# MotorController_ToniDove_Full05.net
KiCad netlist of a schematic drawn in EAGLE
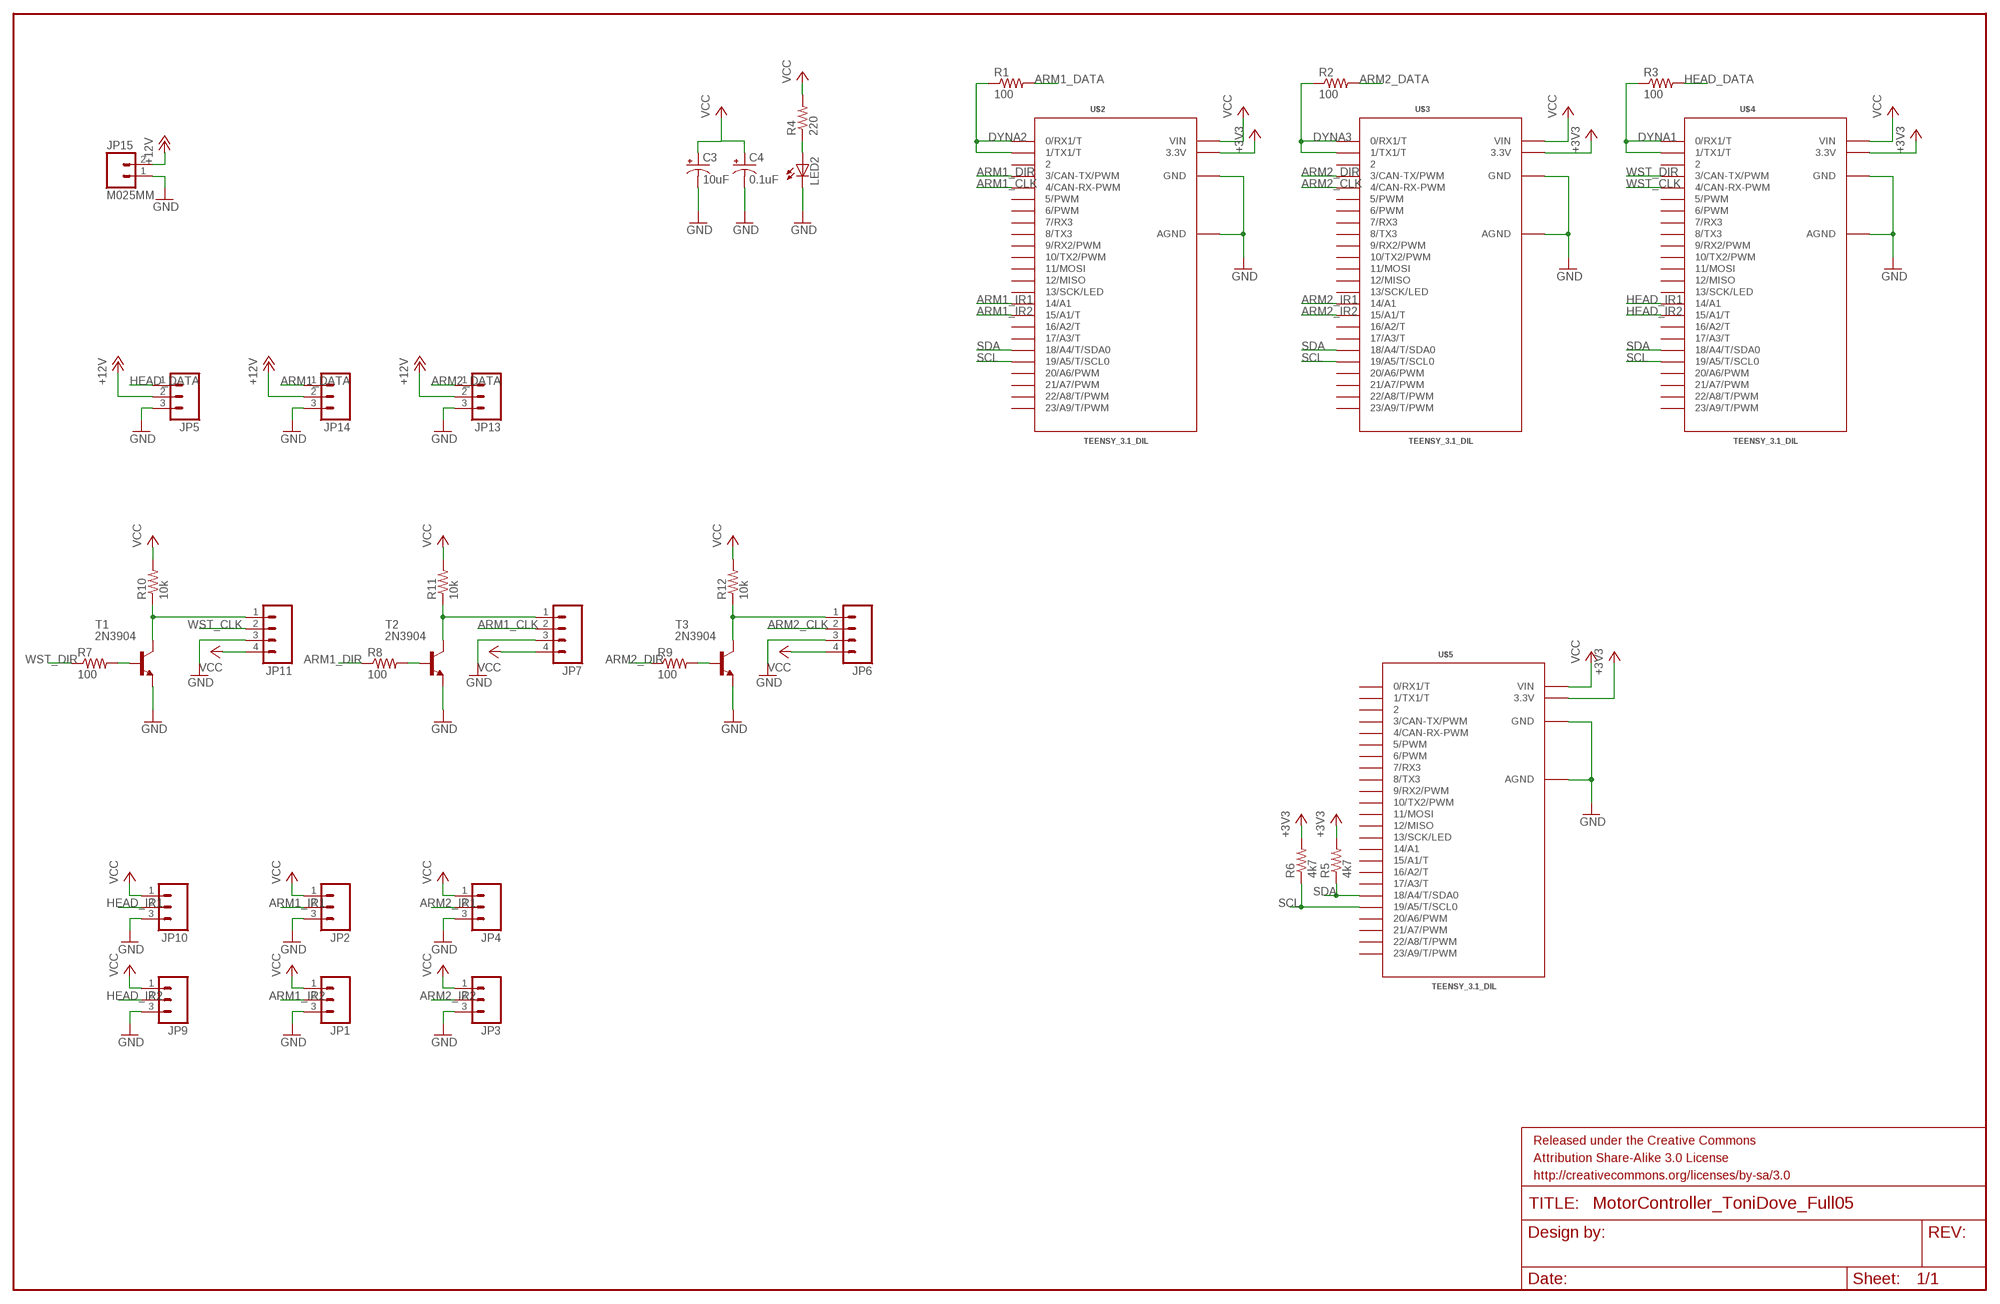
[diagram p0: schematic, sheet 1]

(export (version "E")
  (design (tool "Eeschema 10.0.6"))
  (components
    (comp (ref "C3")
      (value "10uF")
      (footprint "eagle-import:E2,5-6E")
      (libsource (lib "eagle-import") (part "CPOL-USE2,5-6E"))
    )
    (comp (ref "C4")
      (value "0.1uF")
      (footprint "eagle-import:E2,5-6E")
      (libsource (lib "eagle-import") (part "CPOL-USE2,5-6E"))
    )
    (comp (ref "FRAME1")
      (value "FRAME-LEDGER")
      (footprint "eagle-import:CREATIVE_COMMONS")
      (libsource (lib "eagle-import") (part "FRAME-LEDGER"))
    )
    (comp (ref "JP1")
      (value "M03PTH")
      (footprint "eagle-import:1X03")
      (libsource (lib "eagle-import") (part "M03PTH"))
    )
    (comp (ref "JP2")
      (value "M03PTH")
      (footprint "eagle-import:1X03")
      (libsource (lib "eagle-import") (part "M03PTH"))
    )
    (comp (ref "JP3")
      (value "M03PTH")
      (footprint "eagle-import:1X03")
      (libsource (lib "eagle-import") (part "M03PTH"))
    )
    (comp (ref "JP4")
      (value "M03PTH")
      (footprint "eagle-import:1X03")
      (libsource (lib "eagle-import") (part "M03PTH"))
    )
    (comp (ref "JP5")
      (value "M03PTH")
      (footprint "eagle-import:1X03")
      (libsource (lib "eagle-import") (part "M03PTH"))
    )
    (comp (ref "JP6")
      (value "M04SCREW")
      (footprint "eagle-import:SCREWTERMINAL-3.5MM-4")
      (libsource (lib "eagle-import") (part "M04SCREW"))
    )
    (comp (ref "JP7")
      (value "M04SCREW")
      (footprint "eagle-import:SCREWTERMINAL-3.5MM-4")
      (libsource (lib "eagle-import") (part "M04SCREW"))
    )
    (comp (ref "JP9")
      (value "M03PTH")
      (footprint "eagle-import:1X03")
      (libsource (lib "eagle-import") (part "M03PTH"))
    )
    (comp (ref "JP10")
      (value "M03PTH")
      (footprint "eagle-import:1X03")
      (libsource (lib "eagle-import") (part "M03PTH"))
    )
    (comp (ref "JP11")
      (value "M04SCREW")
      (footprint "eagle-import:SCREWTERMINAL-3.5MM-4")
      (libsource (lib "eagle-import") (part "M04SCREW"))
    )
    (comp (ref "JP13")
      (value "M03PTH")
      (footprint "eagle-import:1X03")
      (libsource (lib "eagle-import") (part "M03PTH"))
    )
    (comp (ref "JP14")
      (value "M03PTH")
      (footprint "eagle-import:1X03")
      (libsource (lib "eagle-import") (part "M03PTH"))
    )
    (comp (ref "JP15")
      (value "M025MM")
      (footprint "eagle-import:SCREWTERMINAL-5MM-2")
      (libsource (lib "eagle-import") (part "M025MM"))
    )
    (comp (ref "LED2")
      (value "LED5MM")
      (footprint "eagle-import:LED5MM")
      (libsource (lib "eagle-import") (part "LED5MM"))
    )
    (comp (ref "R1")
      (value "100")
      (footprint "eagle-import:0204_7")
      (libsource (lib "eagle-import") (part "R-US_0204/7"))
    )
    (comp (ref "R2")
      (value "100")
      (footprint "eagle-import:0204_7")
      (libsource (lib "eagle-import") (part "R-US_0204/7"))
    )
    (comp (ref "R3")
      (value "100")
      (footprint "eagle-import:0204_7")
      (libsource (lib "eagle-import") (part "R-US_0204/7"))
    )
    (comp (ref "R4")
      (value "220")
      (footprint "eagle-import:0204_7")
      (libsource (lib "eagle-import") (part "R-US_0204/7"))
    )
    (comp (ref "R5")
      (value "4k7")
      (footprint "eagle-import:0204_7")
      (libsource (lib "eagle-import") (part "R-US_0204/7"))
    )
    (comp (ref "R6")
      (value "4k7")
      (footprint "eagle-import:0204_7")
      (libsource (lib "eagle-import") (part "R-US_0204/7"))
    )
    (comp (ref "R7")
      (value "100")
      (footprint "eagle-import:0204_7")
      (libsource (lib "eagle-import") (part "R-US_0204/7"))
    )
    (comp (ref "R8")
      (value "100")
      (footprint "eagle-import:0204_7")
      (libsource (lib "eagle-import") (part "R-US_0204/7"))
    )
    (comp (ref "R9")
      (value "100")
      (footprint "eagle-import:0204_7")
      (libsource (lib "eagle-import") (part "R-US_0204/7"))
    )
    (comp (ref "R10")
      (value "10k")
      (footprint "eagle-import:0204_7")
      (libsource (lib "eagle-import") (part "R-US_0204/7"))
    )
    (comp (ref "R11")
      (value "10k")
      (footprint "eagle-import:0204_7")
      (libsource (lib "eagle-import") (part "R-US_0204/7"))
    )
    (comp (ref "R12")
      (value "10k")
      (footprint "eagle-import:0204_7")
      (libsource (lib "eagle-import") (part "R-US_0204/7"))
    )
    (comp (ref "T1")
      (value "2N3904")
      (footprint "eagle-import:TO92")
      (libsource (lib "eagle-import") (part "2N3904"))
    )
    (comp (ref "T2")
      (value "2N3904")
      (footprint "eagle-import:TO92")
      (libsource (lib "eagle-import") (part "2N3904"))
    )
    (comp (ref "T3")
      (value "2N3904")
      (footprint "eagle-import:TO92")
      (libsource (lib "eagle-import") (part "2N3904"))
    )
    (comp (ref "U$2")
      (value "TEENSY_3.1_DIL")
      (footprint "eagle-import:TEENSY3-DIL")
      (libsource (lib "eagle-import") (part "TEENSY_3.1_DIL"))
    )
    (comp (ref "U$3")
      (value "TEENSY_3.1_DIL")
      (footprint "eagle-import:TEENSY3-DIL")
      (libsource (lib "eagle-import") (part "TEENSY_3.1_DIL"))
    )
    (comp (ref "U$4")
      (value "TEENSY_3.1_DIL")
      (footprint "eagle-import:TEENSY3-DIL")
      (libsource (lib "eagle-import") (part "TEENSY_3.1_DIL"))
    )
    (comp (ref "U$5")
      (value "TEENSY_3.1_DIL")
      (footprint "eagle-import:TEENSY3-DIL")
      (libsource (lib "eagle-import") (part "TEENSY_3.1_DIL"))
    )
  )
  (nets
    (net (code "1") (name "+3V3") (class "Default")
      (node (ref "R5") (pin "2") (pinfunction "2_2") (pintype "passive"))
      (node (ref "R6") (pin "2") (pinfunction "2_2") (pintype "passive"))
      (node (ref "U$2") (pin "3.3V") (pinfunction "3.3V_3.3V") (pintype "power_in"))
      (node (ref "U$3") (pin "3.3V") (pinfunction "3.3V_3.3V") (pintype "power_in"))
      (node (ref "U$4") (pin "3.3V") (pinfunction "3.3V_3.3V") (pintype "power_in"))
      (node (ref "U$5") (pin "3.3V") (pinfunction "3.3V_3.3V") (pintype "power_in"))
    )
    (net (code "2") (name "+12V") (class "Default")
      (node (ref "JP13") (pin "2") (pinfunction "2_2") (pintype "passive"))
      (node (ref "JP14") (pin "2") (pinfunction "2_2") (pintype "passive"))
      (node (ref "JP15") (pin "2") (pinfunction "2_2") (pintype "passive"))
      (node (ref "JP5") (pin "2") (pinfunction "2_2") (pintype "passive"))
    )
    (net (code "3") (name "/ARM1_CLK") (class "Default")
      (node (ref "JP7") (pin "2") (pinfunction "2_2") (pintype "passive"))
      (node (ref "U$2") (pin "4") (pinfunction "4/CAN-RX-PWM_4") (pintype "bidirectional"))
    )
    (net (code "4") (name "/ARM1_DATA") (class "Default")
      (node (ref "JP14") (pin "1") (pinfunction "1_1") (pintype "passive"))
      (node (ref "R1") (pin "2") (pinfunction "2_2") (pintype "passive"))
    )
    (net (code "5") (name "/ARM1_DIR") (class "Default")
      (node (ref "R8") (pin "1") (pinfunction "1_1") (pintype "passive"))
      (node (ref "U$2") (pin "3") (pinfunction "3/CAN-TX/PWM_3") (pintype "bidirectional"))
    )
    (net (code "6") (name "/ARM1_IR1") (class "Default")
      (node (ref "JP2") (pin "2") (pinfunction "2_2") (pintype "passive"))
      (node (ref "U$2") (pin "14/A0") (pinfunction "14/A1_14/A0") (pintype "bidirectional"))
    )
    (net (code "7") (name "/ARM1_IR2") (class "Default")
      (node (ref "JP1") (pin "2") (pinfunction "2_2") (pintype "passive"))
      (node (ref "U$2") (pin "15/A1") (pinfunction "15/A1/T_15/A1") (pintype "bidirectional"))
    )
    (net (code "8") (name "/ARM2_CLK") (class "Default")
      (node (ref "JP6") (pin "2") (pinfunction "2_2") (pintype "passive"))
      (node (ref "U$3") (pin "4") (pinfunction "4/CAN-RX-PWM_4") (pintype "bidirectional"))
    )
    (net (code "9") (name "/ARM2_DATA") (class "Default")
      (node (ref "JP13") (pin "1") (pinfunction "1_1") (pintype "passive"))
      (node (ref "R2") (pin "2") (pinfunction "2_2") (pintype "passive"))
    )
    (net (code "10") (name "/ARM2_DIR") (class "Default")
      (node (ref "R9") (pin "1") (pinfunction "1_1") (pintype "passive"))
      (node (ref "U$3") (pin "3") (pinfunction "3/CAN-TX/PWM_3") (pintype "bidirectional"))
    )
    (net (code "11") (name "/ARM2_IR1") (class "Default")
      (node (ref "JP4") (pin "2") (pinfunction "2_2") (pintype "passive"))
      (node (ref "U$3") (pin "14/A0") (pinfunction "14/A1_14/A0") (pintype "bidirectional"))
    )
    (net (code "12") (name "/ARM2_IR2") (class "Default")
      (node (ref "JP3") (pin "2") (pinfunction "2_2") (pintype "passive"))
      (node (ref "U$3") (pin "15/A1") (pinfunction "15/A1/T_15/A1") (pintype "bidirectional"))
    )
    (net (code "13") (name "/DYNA1") (class "Default")
      (node (ref "R3") (pin "1") (pinfunction "1_1") (pintype "passive"))
      (node (ref "U$4") (pin "0") (pinfunction "0/RX1/T_0") (pintype "bidirectional"))
      (node (ref "U$4") (pin "1") (pinfunction "1/TX1/T_1") (pintype "bidirectional"))
    )
    (net (code "14") (name "/DYNA2") (class "Default")
      (node (ref "R1") (pin "1") (pinfunction "1_1") (pintype "passive"))
      (node (ref "U$2") (pin "0") (pinfunction "0/RX1/T_0") (pintype "bidirectional"))
      (node (ref "U$2") (pin "1") (pinfunction "1/TX1/T_1") (pintype "bidirectional"))
    )
    (net (code "15") (name "/DYNA3") (class "Default")
      (node (ref "R2") (pin "1") (pinfunction "1_1") (pintype "passive"))
      (node (ref "U$3") (pin "0") (pinfunction "0/RX1/T_0") (pintype "bidirectional"))
      (node (ref "U$3") (pin "1") (pinfunction "1/TX1/T_1") (pintype "bidirectional"))
    )
    (net (code "16") (name "/HEAD_DATA") (class "Default")
      (node (ref "JP5") (pin "1") (pinfunction "1_1") (pintype "passive"))
      (node (ref "R3") (pin "2") (pinfunction "2_2") (pintype "passive"))
    )
    (net (code "17") (name "/HEAD_IR1") (class "Default")
      (node (ref "JP10") (pin "2") (pinfunction "2_2") (pintype "passive"))
      (node (ref "U$4") (pin "14/A0") (pinfunction "14/A1_14/A0") (pintype "bidirectional"))
    )
    (net (code "18") (name "/HEAD_IR2") (class "Default")
      (node (ref "JP9") (pin "2") (pinfunction "2_2") (pintype "passive"))
      (node (ref "U$4") (pin "15/A1") (pinfunction "15/A1/T_15/A1") (pintype "bidirectional"))
    )
    (net (code "19") (name "/SCL") (class "Default")
      (node (ref "R6") (pin "1") (pinfunction "1_1") (pintype "passive"))
      (node (ref "U$2") (pin "19/A5") (pinfunction "19/A5/T/SCL0_19/A5") (pintype "bidirectional"))
      (node (ref "U$3") (pin "19/A5") (pinfunction "19/A5/T/SCL0_19/A5") (pintype "bidirectional"))
      (node (ref "U$4") (pin "19/A5") (pinfunction "19/A5/T/SCL0_19/A5") (pintype "bidirectional"))
      (node (ref "U$5") (pin "19/A5") (pinfunction "19/A5/T/SCL0_19/A5") (pintype "bidirectional"))
    )
    (net (code "20") (name "/SDA") (class "Default")
      (node (ref "R5") (pin "1") (pinfunction "1_1") (pintype "passive"))
      (node (ref "U$2") (pin "18/A4") (pinfunction "18/A4/T/SDA0_18/A4") (pintype "bidirectional"))
      (node (ref "U$3") (pin "18/A4") (pinfunction "18/A4/T/SDA0_18/A4") (pintype "bidirectional"))
      (node (ref "U$4") (pin "18/A4") (pinfunction "18/A4/T/SDA0_18/A4") (pintype "bidirectional"))
      (node (ref "U$5") (pin "18/A4") (pinfunction "18/A4/T/SDA0_18/A4") (pintype "bidirectional"))
    )
    (net (code "21") (name "/WST_CLK") (class "Default")
      (node (ref "JP11") (pin "2") (pinfunction "2_2") (pintype "passive"))
      (node (ref "U$4") (pin "4") (pinfunction "4/CAN-RX-PWM_4") (pintype "bidirectional"))
    )
    (net (code "22") (name "/WST_DIR") (class "Default")
      (node (ref "R7") (pin "1") (pinfunction "1_1") (pintype "passive"))
      (node (ref "U$4") (pin "3") (pinfunction "3/CAN-TX/PWM_3") (pintype "bidirectional"))
    )
    (net (code "23") (name "GND") (class "Default")
      (node (ref "C3") (pin "-") (pinfunction "-_-") (pintype "passive"))
      (node (ref "C4") (pin "-") (pinfunction "-_-") (pintype "passive"))
      (node (ref "JP1") (pin "3") (pinfunction "3_3") (pintype "passive"))
      (node (ref "JP10") (pin "3") (pinfunction "3_3") (pintype "passive"))
      (node (ref "JP11") (pin "3") (pinfunction "3_3") (pintype "passive"))
      (node (ref "JP13") (pin "3") (pinfunction "3_3") (pintype "passive"))
      (node (ref "JP14") (pin "3") (pinfunction "3_3") (pintype "passive"))
      (node (ref "JP15") (pin "1") (pinfunction "1_1") (pintype "passive"))
      (node (ref "JP2") (pin "3") (pinfunction "3_3") (pintype "passive"))
      (node (ref "JP3") (pin "3") (pinfunction "3_3") (pintype "passive"))
      (node (ref "JP4") (pin "3") (pinfunction "3_3") (pintype "passive"))
      (node (ref "JP5") (pin "3") (pinfunction "3_3") (pintype "passive"))
      (node (ref "JP6") (pin "3") (pinfunction "3_3") (pintype "passive"))
      (node (ref "JP7") (pin "3") (pinfunction "3_3") (pintype "passive"))
      (node (ref "JP9") (pin "3") (pinfunction "3_3") (pintype "passive"))
      (node (ref "LED2") (pin "K") (pinfunction "C_K") (pintype "passive"))
      (node (ref "T1") (pin "3") (pinfunction "E_3") (pintype "passive"))
      (node (ref "T2") (pin "3") (pinfunction "E_3") (pintype "passive"))
      (node (ref "T3") (pin "3") (pinfunction "E_3") (pintype "passive"))
      (node (ref "U$2") (pin "AGND") (pinfunction "AGND_AGND") (pintype "power_in"))
      (node (ref "U$2") (pin "GND") (pinfunction "GND_GND") (pintype "power_in"))
      (node (ref "U$3") (pin "AGND") (pinfunction "AGND_AGND") (pintype "power_in"))
      (node (ref "U$3") (pin "GND") (pinfunction "GND_GND") (pintype "power_in"))
      (node (ref "U$4") (pin "AGND") (pinfunction "AGND_AGND") (pintype "power_in"))
      (node (ref "U$4") (pin "GND") (pinfunction "GND_GND") (pintype "power_in"))
      (node (ref "U$5") (pin "AGND") (pinfunction "AGND_AGND") (pintype "power_in"))
      (node (ref "U$5") (pin "GND") (pinfunction "GND_GND") (pintype "power_in"))
    )
    (net (code "24") (name "Net-(LED2-PadA)") (class "Default")
      (node (ref "LED2") (pin "A") (pinfunction "A_A") (pintype "passive"))
      (node (ref "R4") (pin "1") (pinfunction "1_1") (pintype "passive"))
    )
    (net (code "25") (name "Net-(T1-B)") (class "Default")
      (node (ref "R7") (pin "2") (pinfunction "2_2") (pintype "passive"))
      (node (ref "T1") (pin "2") (pinfunction "B_2") (pintype "passive"))
    )
    (net (code "26") (name "Net-(T1-C)") (class "Default")
      (node (ref "JP11") (pin "1") (pinfunction "1_1") (pintype "passive"))
      (node (ref "R10") (pin "1") (pinfunction "1_1") (pintype "passive"))
      (node (ref "T1") (pin "1") (pinfunction "C_1") (pintype "passive"))
    )
    (net (code "27") (name "Net-(T2-B)") (class "Default")
      (node (ref "R8") (pin "2") (pinfunction "2_2") (pintype "passive"))
      (node (ref "T2") (pin "2") (pinfunction "B_2") (pintype "passive"))
    )
    (net (code "28") (name "Net-(T2-C)") (class "Default")
      (node (ref "JP7") (pin "1") (pinfunction "1_1") (pintype "passive"))
      (node (ref "R11") (pin "1") (pinfunction "1_1") (pintype "passive"))
      (node (ref "T2") (pin "1") (pinfunction "C_1") (pintype "passive"))
    )
    (net (code "29") (name "Net-(T3-B)") (class "Default")
      (node (ref "R9") (pin "2") (pinfunction "2_2") (pintype "passive"))
      (node (ref "T3") (pin "2") (pinfunction "B_2") (pintype "passive"))
    )
    (net (code "30") (name "Net-(T3-C)") (class "Default")
      (node (ref "JP6") (pin "1") (pinfunction "1_1") (pintype "passive"))
      (node (ref "R12") (pin "1") (pinfunction "1_1") (pintype "passive"))
      (node (ref "T3") (pin "1") (pinfunction "C_1") (pintype "passive"))
    )
    (net (code "31") (name "VCC") (class "Default")
      (node (ref "C3") (pin "+") (pinfunction "+_+") (pintype "passive"))
      (node (ref "C4") (pin "+") (pinfunction "+_+") (pintype "passive"))
      (node (ref "JP1") (pin "1") (pinfunction "1_1") (pintype "passive"))
      (node (ref "JP10") (pin "1") (pinfunction "1_1") (pintype "passive"))
      (node (ref "JP11") (pin "4") (pinfunction "4_4") (pintype "passive"))
      (node (ref "JP2") (pin "1") (pinfunction "1_1") (pintype "passive"))
      (node (ref "JP3") (pin "1") (pinfunction "1_1") (pintype "passive"))
      (node (ref "JP4") (pin "1") (pinfunction "1_1") (pintype "passive"))
      (node (ref "JP6") (pin "4") (pinfunction "4_4") (pintype "passive"))
      (node (ref "JP7") (pin "4") (pinfunction "4_4") (pintype "passive"))
      (node (ref "JP9") (pin "1") (pinfunction "1_1") (pintype "passive"))
      (node (ref "R10") (pin "2") (pinfunction "2_2") (pintype "passive"))
      (node (ref "R11") (pin "2") (pinfunction "2_2") (pintype "passive"))
      (node (ref "R12") (pin "2") (pinfunction "2_2") (pintype "passive"))
      (node (ref "R4") (pin "2") (pinfunction "2_2") (pintype "passive"))
      (node (ref "U$2") (pin "VIN") (pinfunction "VIN_VIN") (pintype "power_in"))
      (node (ref "U$3") (pin "VIN") (pinfunction "VIN_VIN") (pintype "power_in"))
      (node (ref "U$4") (pin "VIN") (pinfunction "VIN_VIN") (pintype "power_in"))
      (node (ref "U$5") (pin "VIN") (pinfunction "VIN_VIN") (pintype "power_in"))
    )
    (net (code "32") (name "unconnected-(U$2-5{slash}PWM-Pad5)") (class "Default")
      (node (ref "U$2") (pin "5") (pinfunction "5/PWM_5") (pintype "bidirectional"))
    )
    (net (code "33") (name "unconnected-(U$2-6{slash}PWM-Pad6)") (class "Default")
      (node (ref "U$2") (pin "6") (pinfunction "6/PWM_6") (pintype "bidirectional"))
    )
    (net (code "34") (name "unconnected-(U$2-7{slash}RX3-Pad7)") (class "Default")
      (node (ref "U$2") (pin "7") (pinfunction "7/RX3_7") (pintype "bidirectional"))
    )
    (net (code "35") (name "unconnected-(U$2-8{slash}TX3-Pad8)") (class "Default")
      (node (ref "U$2") (pin "8") (pinfunction "8/TX3_8") (pintype "bidirectional"))
    )
    (net (code "36") (name "unconnected-(U$2-9{slash}RX2{slash}PWM-Pad9)") (class "Default")
      (node (ref "U$2") (pin "9") (pinfunction "9/RX2/PWM_9") (pintype "bidirectional"))
    )
    (net (code "37") (name "unconnected-(U$2-10{slash}TX2{slash}PWM-Pad10)") (class "Default")
      (node (ref "U$2") (pin "10") (pinfunction "10/TX2/PWM_10") (pintype "bidirectional"))
    )
    (net (code "38") (name "unconnected-(U$2-11{slash}MOSI-Pad11)") (class "Default")
      (node (ref "U$2") (pin "11") (pinfunction "11/MOSI_11") (pintype "bidirectional"))
    )
    (net (code "39") (name "unconnected-(U$2-12{slash}MISO-Pad12)") (class "Default")
      (node (ref "U$2") (pin "12") (pinfunction "12/MISO_12") (pintype "bidirectional"))
    )
    (net (code "40") (name "unconnected-(U$2-13{slash}SCK{slash}LED-Pad13)") (class "Default")
      (node (ref "U$2") (pin "13") (pinfunction "13/SCK/LED_13") (pintype "bidirectional"))
    )
    (net (code "41") (name "unconnected-(U$2-16{slash}A2{slash}T-Pad16{slash}A2)") (class "Default")
      (node (ref "U$2") (pin "16/A2") (pinfunction "16/A2/T_16/A2") (pintype "bidirectional"))
    )
    (net (code "42") (name "unconnected-(U$2-17{slash}A3{slash}T-Pad17{slash}A3)") (class "Default")
      (node (ref "U$2") (pin "17/A3") (pinfunction "17/A3/T_17/A3") (pintype "bidirectional"))
    )
    (net (code "43") (name "unconnected-(U$2-20{slash}A6{slash}PWM-Pad20{slash}A6)") (class "Default")
      (node (ref "U$2") (pin "20/A6") (pinfunction "20/A6/PWM_20/A6") (pintype "bidirectional"))
    )
    (net (code "44") (name "unconnected-(U$2-21{slash}A7{slash}PWM-Pad21{slash}A7)") (class "Default")
      (node (ref "U$2") (pin "21/A7") (pinfunction "21/A7/PWM_21/A7") (pintype "bidirectional"))
    )
    (net (code "45") (name "unconnected-(U$2-22{slash}A8{slash}T{slash}PWM-Pad22{slash}A8)") (class "Default")
      (node (ref "U$2") (pin "22/A8") (pinfunction "22/A8/T/PWM_22/A8") (pintype "bidirectional"))
    )
    (net (code "46") (name "unconnected-(U$2-23{slash}A9{slash}T{slash}PWM-Pad23{slash}A9)") (class "Default")
      (node (ref "U$2") (pin "23/A9") (pinfunction "23/A9/T/PWM_23/A9") (pintype "bidirectional"))
    )
    (net (code "47") (name "unconnected-(U$2-Pad2)") (class "Default")
      (node (ref "U$2") (pin "2") (pinfunction "2_2") (pintype "bidirectional"))
    )
    (net (code "48") (name "unconnected-(U$3-5{slash}PWM-Pad5)") (class "Default")
      (node (ref "U$3") (pin "5") (pinfunction "5/PWM_5") (pintype "bidirectional"))
    )
    (net (code "49") (name "unconnected-(U$3-6{slash}PWM-Pad6)") (class "Default")
      (node (ref "U$3") (pin "6") (pinfunction "6/PWM_6") (pintype "bidirectional"))
    )
    (net (code "50") (name "unconnected-(U$3-7{slash}RX3-Pad7)") (class "Default")
      (node (ref "U$3") (pin "7") (pinfunction "7/RX3_7") (pintype "bidirectional"))
    )
    (net (code "51") (name "unconnected-(U$3-8{slash}TX3-Pad8)") (class "Default")
      (node (ref "U$3") (pin "8") (pinfunction "8/TX3_8") (pintype "bidirectional"))
    )
    (net (code "52") (name "unconnected-(U$3-9{slash}RX2{slash}PWM-Pad9)") (class "Default")
      (node (ref "U$3") (pin "9") (pinfunction "9/RX2/PWM_9") (pintype "bidirectional"))
    )
    (net (code "53") (name "unconnected-(U$3-10{slash}TX2{slash}PWM-Pad10)") (class "Default")
      (node (ref "U$3") (pin "10") (pinfunction "10/TX2/PWM_10") (pintype "bidirectional"))
    )
    (net (code "54") (name "unconnected-(U$3-11{slash}MOSI-Pad11)") (class "Default")
      (node (ref "U$3") (pin "11") (pinfunction "11/MOSI_11") (pintype "bidirectional"))
    )
    (net (code "55") (name "unconnected-(U$3-12{slash}MISO-Pad12)") (class "Default")
      (node (ref "U$3") (pin "12") (pinfunction "12/MISO_12") (pintype "bidirectional"))
    )
    (net (code "56") (name "unconnected-(U$3-13{slash}SCK{slash}LED-Pad13)") (class "Default")
      (node (ref "U$3") (pin "13") (pinfunction "13/SCK/LED_13") (pintype "bidirectional"))
    )
    (net (code "57") (name "unconnected-(U$3-16{slash}A2{slash}T-Pad16{slash}A2)") (class "Default")
      (node (ref "U$3") (pin "16/A2") (pinfunction "16/A2/T_16/A2") (pintype "bidirectional"))
    )
    (net (code "58") (name "unconnected-(U$3-17{slash}A3{slash}T-Pad17{slash}A3)") (class "Default")
      (node (ref "U$3") (pin "17/A3") (pinfunction "17/A3/T_17/A3") (pintype "bidirectional"))
    )
    (net (code "59") (name "unconnected-(U$3-20{slash}A6{slash}PWM-Pad20{slash}A6)") (class "Default")
      (node (ref "U$3") (pin "20/A6") (pinfunction "20/A6/PWM_20/A6") (pintype "bidirectional"))
    )
    (net (code "60") (name "unconnected-(U$3-21{slash}A7{slash}PWM-Pad21{slash}A7)") (class "Default")
      (node (ref "U$3") (pin "21/A7") (pinfunction "21/A7/PWM_21/A7") (pintype "bidirectional"))
    )
    (net (code "61") (name "unconnected-(U$3-22{slash}A8{slash}T{slash}PWM-Pad22{slash}A8)") (class "Default")
      (node (ref "U$3") (pin "22/A8") (pinfunction "22/A8/T/PWM_22/A8") (pintype "bidirectional"))
    )
    (net (code "62") (name "unconnected-(U$3-23{slash}A9{slash}T{slash}PWM-Pad23{slash}A9)") (class "Default")
      (node (ref "U$3") (pin "23/A9") (pinfunction "23/A9/T/PWM_23/A9") (pintype "bidirectional"))
    )
    (net (code "63") (name "unconnected-(U$3-Pad2)") (class "Default")
      (node (ref "U$3") (pin "2") (pinfunction "2_2") (pintype "bidirectional"))
    )
    (net (code "64") (name "unconnected-(U$4-5{slash}PWM-Pad5)") (class "Default")
      (node (ref "U$4") (pin "5") (pinfunction "5/PWM_5") (pintype "bidirectional"))
    )
    (net (code "65") (name "unconnected-(U$4-6{slash}PWM-Pad6)") (class "Default")
      (node (ref "U$4") (pin "6") (pinfunction "6/PWM_6") (pintype "bidirectional"))
    )
    (net (code "66") (name "unconnected-(U$4-7{slash}RX3-Pad7)") (class "Default")
      (node (ref "U$4") (pin "7") (pinfunction "7/RX3_7") (pintype "bidirectional"))
    )
    (net (code "67") (name "unconnected-(U$4-8{slash}TX3-Pad8)") (class "Default")
      (node (ref "U$4") (pin "8") (pinfunction "8/TX3_8") (pintype "bidirectional"))
    )
    (net (code "68") (name "unconnected-(U$4-9{slash}RX2{slash}PWM-Pad9)") (class "Default")
      (node (ref "U$4") (pin "9") (pinfunction "9/RX2/PWM_9") (pintype "bidirectional"))
    )
    (net (code "69") (name "unconnected-(U$4-10{slash}TX2{slash}PWM-Pad10)") (class "Default")
      (node (ref "U$4") (pin "10") (pinfunction "10/TX2/PWM_10") (pintype "bidirectional"))
    )
    (net (code "70") (name "unconnected-(U$4-11{slash}MOSI-Pad11)") (class "Default")
      (node (ref "U$4") (pin "11") (pinfunction "11/MOSI_11") (pintype "bidirectional"))
    )
    (net (code "71") (name "unconnected-(U$4-12{slash}MISO-Pad12)") (class "Default")
      (node (ref "U$4") (pin "12") (pinfunction "12/MISO_12") (pintype "bidirectional"))
    )
    (net (code "72") (name "unconnected-(U$4-13{slash}SCK{slash}LED-Pad13)") (class "Default")
      (node (ref "U$4") (pin "13") (pinfunction "13/SCK/LED_13") (pintype "bidirectional"))
    )
    (net (code "73") (name "unconnected-(U$4-16{slash}A2{slash}T-Pad16{slash}A2)") (class "Default")
      (node (ref "U$4") (pin "16/A2") (pinfunction "16/A2/T_16/A2") (pintype "bidirectional"))
    )
    (net (code "74") (name "unconnected-(U$4-17{slash}A3{slash}T-Pad17{slash}A3)") (class "Default")
      (node (ref "U$4") (pin "17/A3") (pinfunction "17/A3/T_17/A3") (pintype "bidirectional"))
    )
    (net (code "75") (name "unconnected-(U$4-20{slash}A6{slash}PWM-Pad20{slash}A6)") (class "Default")
      (node (ref "U$4") (pin "20/A6") (pinfunction "20/A6/PWM_20/A6") (pintype "bidirectional"))
    )
    (net (code "76") (name "unconnected-(U$4-21{slash}A7{slash}PWM-Pad21{slash}A7)") (class "Default")
      (node (ref "U$4") (pin "21/A7") (pinfunction "21/A7/PWM_21/A7") (pintype "bidirectional"))
    )
    (net (code "77") (name "unconnected-(U$4-22{slash}A8{slash}T{slash}PWM-Pad22{slash}A8)") (class "Default")
      (node (ref "U$4") (pin "22/A8") (pinfunction "22/A8/T/PWM_22/A8") (pintype "bidirectional"))
    )
    (net (code "78") (name "unconnected-(U$4-23{slash}A9{slash}T{slash}PWM-Pad23{slash}A9)") (class "Default")
      (node (ref "U$4") (pin "23/A9") (pinfunction "23/A9/T/PWM_23/A9") (pintype "bidirectional"))
    )
    (net (code "79") (name "unconnected-(U$4-Pad2)") (class "Default")
      (node (ref "U$4") (pin "2") (pinfunction "2_2") (pintype "bidirectional"))
    )
    (net (code "80") (name "unconnected-(U$5-0{slash}RX1{slash}T-Pad0)") (class "Default")
      (node (ref "U$5") (pin "0") (pinfunction "0/RX1/T_0") (pintype "bidirectional"))
    )
    (net (code "81") (name "unconnected-(U$5-1{slash}TX1{slash}T-Pad1)") (class "Default")
      (node (ref "U$5") (pin "1") (pinfunction "1/TX1/T_1") (pintype "bidirectional"))
    )
    (net (code "82") (name "unconnected-(U$5-3{slash}CAN-TX{slash}PWM-Pad3)") (class "Default")
      (node (ref "U$5") (pin "3") (pinfunction "3/CAN-TX/PWM_3") (pintype "bidirectional"))
    )
    (net (code "83") (name "unconnected-(U$5-4{slash}CAN-RX-PWM-Pad4)") (class "Default")
      (node (ref "U$5") (pin "4") (pinfunction "4/CAN-RX-PWM_4") (pintype "bidirectional"))
    )
    (net (code "84") (name "unconnected-(U$5-5{slash}PWM-Pad5)") (class "Default")
      (node (ref "U$5") (pin "5") (pinfunction "5/PWM_5") (pintype "bidirectional"))
    )
    (net (code "85") (name "unconnected-(U$5-6{slash}PWM-Pad6)") (class "Default")
      (node (ref "U$5") (pin "6") (pinfunction "6/PWM_6") (pintype "bidirectional"))
    )
    (net (code "86") (name "unconnected-(U$5-7{slash}RX3-Pad7)") (class "Default")
      (node (ref "U$5") (pin "7") (pinfunction "7/RX3_7") (pintype "bidirectional"))
    )
    (net (code "87") (name "unconnected-(U$5-8{slash}TX3-Pad8)") (class "Default")
      (node (ref "U$5") (pin "8") (pinfunction "8/TX3_8") (pintype "bidirectional"))
    )
    (net (code "88") (name "unconnected-(U$5-9{slash}RX2{slash}PWM-Pad9)") (class "Default")
      (node (ref "U$5") (pin "9") (pinfunction "9/RX2/PWM_9") (pintype "bidirectional"))
    )
    (net (code "89") (name "unconnected-(U$5-10{slash}TX2{slash}PWM-Pad10)") (class "Default")
      (node (ref "U$5") (pin "10") (pinfunction "10/TX2/PWM_10") (pintype "bidirectional"))
    )
    (net (code "90") (name "unconnected-(U$5-11{slash}MOSI-Pad11)") (class "Default")
      (node (ref "U$5") (pin "11") (pinfunction "11/MOSI_11") (pintype "bidirectional"))
    )
    (net (code "91") (name "unconnected-(U$5-12{slash}MISO-Pad12)") (class "Default")
      (node (ref "U$5") (pin "12") (pinfunction "12/MISO_12") (pintype "bidirectional"))
    )
    (net (code "92") (name "unconnected-(U$5-13{slash}SCK{slash}LED-Pad13)") (class "Default")
      (node (ref "U$5") (pin "13") (pinfunction "13/SCK/LED_13") (pintype "bidirectional"))
    )
    (net (code "93") (name "unconnected-(U$5-14{slash}A1-Pad14{slash}A0)") (class "Default")
      (node (ref "U$5") (pin "14/A0") (pinfunction "14/A1_14/A0") (pintype "bidirectional"))
    )
    (net (code "94") (name "unconnected-(U$5-15{slash}A1{slash}T-Pad15{slash}A1)") (class "Default")
      (node (ref "U$5") (pin "15/A1") (pinfunction "15/A1/T_15/A1") (pintype "bidirectional"))
    )
    (net (code "95") (name "unconnected-(U$5-16{slash}A2{slash}T-Pad16{slash}A2)") (class "Default")
      (node (ref "U$5") (pin "16/A2") (pinfunction "16/A2/T_16/A2") (pintype "bidirectional"))
    )
    (net (code "96") (name "unconnected-(U$5-17{slash}A3{slash}T-Pad17{slash}A3)") (class "Default")
      (node (ref "U$5") (pin "17/A3") (pinfunction "17/A3/T_17/A3") (pintype "bidirectional"))
    )
    (net (code "97") (name "unconnected-(U$5-20{slash}A6{slash}PWM-Pad20{slash}A6)") (class "Default")
      (node (ref "U$5") (pin "20/A6") (pinfunction "20/A6/PWM_20/A6") (pintype "bidirectional"))
    )
    (net (code "98") (name "unconnected-(U$5-21{slash}A7{slash}PWM-Pad21{slash}A7)") (class "Default")
      (node (ref "U$5") (pin "21/A7") (pinfunction "21/A7/PWM_21/A7") (pintype "bidirectional"))
    )
    (net (code "99") (name "unconnected-(U$5-22{slash}A8{slash}T{slash}PWM-Pad22{slash}A8)") (class "Default")
      (node (ref "U$5") (pin "22/A8") (pinfunction "22/A8/T/PWM_22/A8") (pintype "bidirectional"))
    )
    (net (code "100") (name "unconnected-(U$5-23{slash}A9{slash}T{slash}PWM-Pad23{slash}A9)") (class "Default")
      (node (ref "U$5") (pin "23/A9") (pinfunction "23/A9/T/PWM_23/A9") (pintype "bidirectional"))
    )
    (net (code "101") (name "unconnected-(U$5-Pad2)") (class "Default")
      (node (ref "U$5") (pin "2") (pinfunction "2_2") (pintype "bidirectional"))
    )
  )
)
